# CPU_USB2_USB3_PHY.net
KiCad netlist of a schematic drawn in Altium Designer
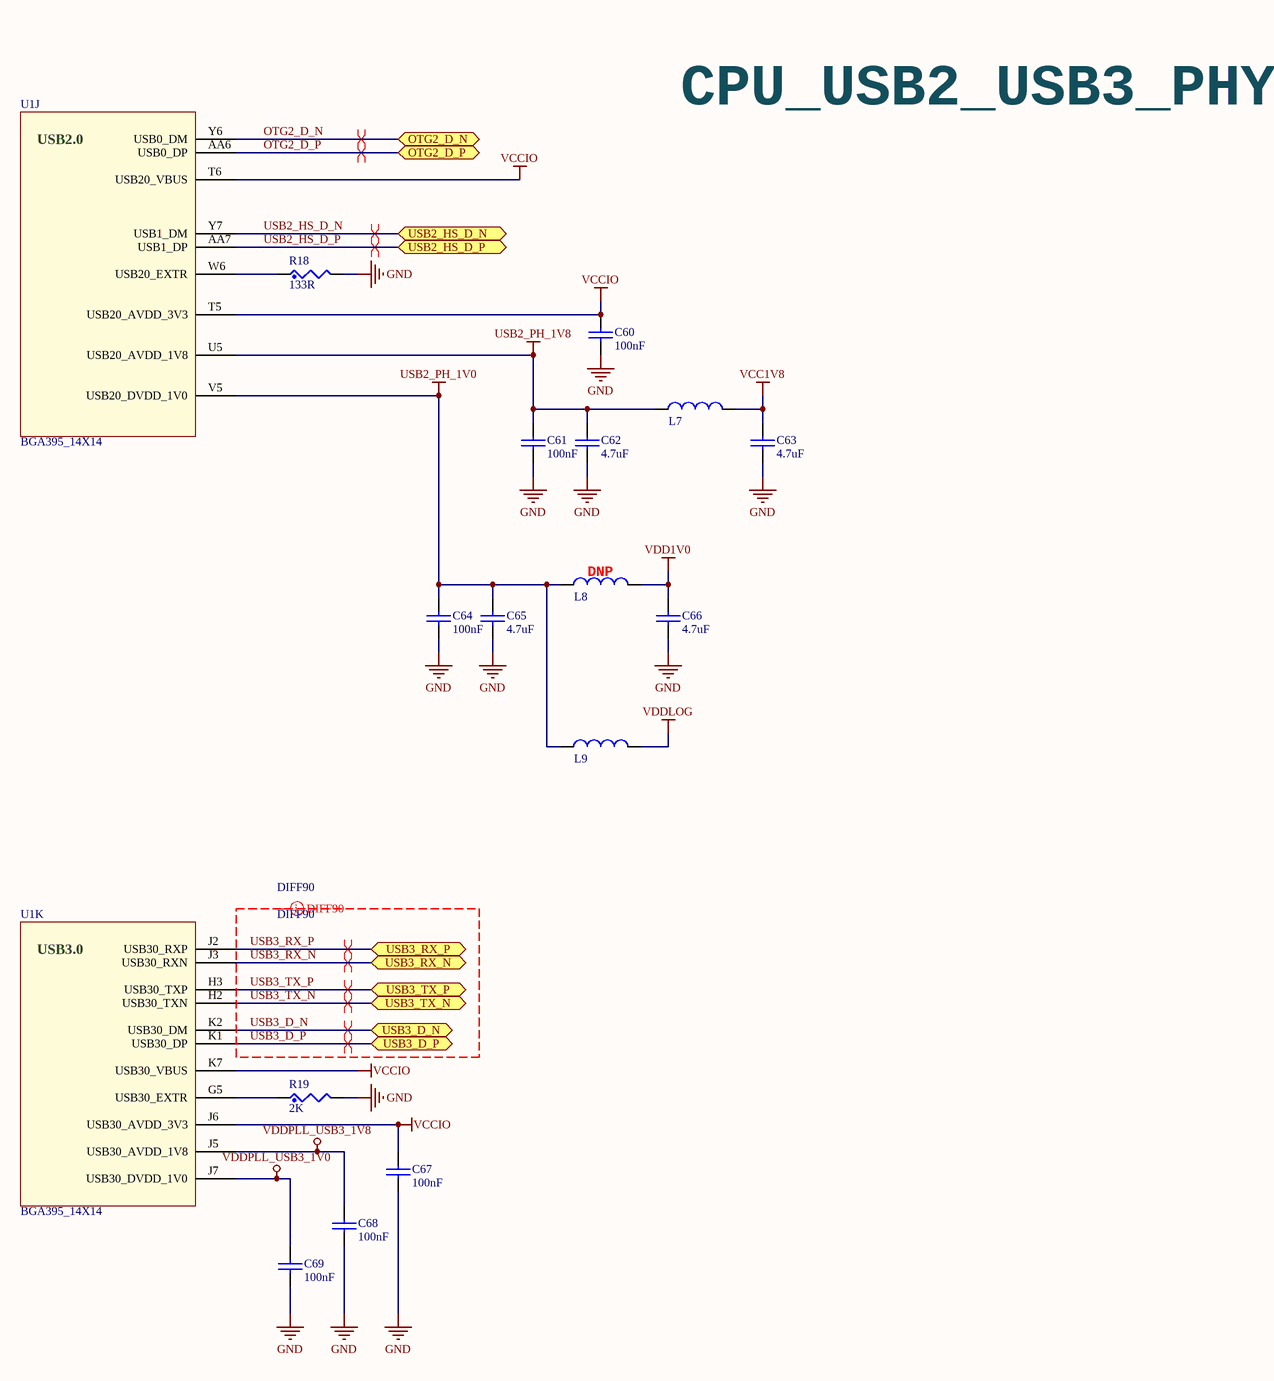
[diagram p0: CPU_USB2_USB3_PHY.SchDoc]

(export (version "E")
  (design (tool "Eeschema 10.0.6"))
  (components
    (comp (ref "C60")
      (value "100nF")
      (footprint "0402_CC - C")
      (libsource (lib "AAR_RockChip_RK3328") (part "CAP_NP"))
    )
    (comp (ref "C61")
      (value "100nF")
      (footprint "0402_CC - C")
      (libsource (lib "AAR_RockChip_RK3328") (part "CAP_NP"))
    )
    (comp (ref "C62")
      (value "4.7uF")
      (footprint "0402_CC - C")
      (libsource (lib "AAR_RockChip_RK3328") (part "CAP_NP"))
    )
    (comp (ref "C63")
      (value "4.7uF")
      (footprint "0402_CC - C")
      (libsource (lib "AAR_RockChip_RK3328") (part "CAP_NP"))
    )
    (comp (ref "C64")
      (value "100nF")
      (footprint "0402_CC - C")
      (libsource (lib "AAR_RockChip_RK3328") (part "CAP_NP"))
    )
    (comp (ref "C65")
      (value "4.7uF")
      (footprint "0402_CC - C")
      (libsource (lib "AAR_RockChip_RK3328") (part "CAP_NP"))
    )
    (comp (ref "C66")
      (value "4.7uF")
      (footprint "0402_CC - C")
      (libsource (lib "AAR_RockChip_RK3328") (part "CAP_NP"))
    )
    (comp (ref "C67")
      (value "100nF")
      (footprint "0402_CC - C")
      (libsource (lib "AAR_RockChip_RK3328") (part "CAP_NP"))
    )
    (comp (ref "C68")
      (value "100nF")
      (footprint "0402_CC - C")
      (libsource (lib "AAR_RockChip_RK3328") (part "CAP_NP"))
    )
    (comp (ref "C69")
      (value "100nF")
      (footprint "0402_CC - C")
      (libsource (lib "AAR_RockChip_RK3328") (part "CAP_NP"))
    )
    (comp (ref "L7")
      (value "INDCHIP")
      (footprint "0603_C_Inductor")
      (description "Fixed Inductors  TDK, By AAR")
      (libsource (lib "AAR_RockChip_RK3328") (part "INDCHIP"))
    )
    (comp (ref "L8")
      (value "INDCHIP")
      (footprint "0603_C_Inductor")
      (description "Fixed Inductors  TDK, By AAR")
      (libsource (lib "AAR_RockChip_RK3328") (part "INDCHIP"))
    )
    (comp (ref "L9")
      (value "INDCHIP")
      (footprint "0603_C_Inductor")
      (description "Fixed Inductors  TDK, By AAR")
      (libsource (lib "AAR_RockChip_RK3328") (part "INDCHIP"))
    )
    (comp (ref "R18")
      (value "133R")
      (footprint "0402_CR")
      (libsource (lib "AAR_RockChip_RK3328") (part "RES"))
    )
    (comp (ref "R19") (value "2K") (footprint "0402_CR") (libsource (lib "AAR_RockChip_RK3328") (part "RES")))
    (comp (ref "U1")
      (value "BGA395_14X14")
      (footprint "BGA395C65P21X21_1750X1750X117")
      (description "By AAR")
      (libsource (lib "AAR_RockChip_RK3328") (part "RK3328"))
    )
  )
  (nets
    (net (code "1") (name "/OTG2_D_N") (class "Default")
      (node (ref "U1") (pin "Y6") (pinfunction "USB0_DM_Y6") (pintype "passive"))
    )
    (net (code "2") (name "/OTG2_D_P") (class "Default")
      (node (ref "U1") (pin "AA6") (pinfunction "USB0_DP_AA6") (pintype "passive"))
    )
    (net (code "3") (name "/USB2_HS_D_N") (class "Default")
      (node (ref "U1") (pin "Y7") (pinfunction "USB1_DM_Y7") (pintype "passive"))
    )
    (net (code "4") (name "/USB2_HS_D_P") (class "Default")
      (node (ref "U1") (pin "AA7") (pinfunction "USB1_DP_AA7") (pintype "passive"))
    )
    (net (code "5") (name "/USB3_D_N") (class "Default")
      (node (ref "U1") (pin "K2") (pinfunction "USB30_DM_K2") (pintype "passive"))
    )
    (net (code "6") (name "/USB3_D_P") (class "Default")
      (node (ref "U1") (pin "K1") (pinfunction "USB30_DP_K1") (pintype "passive"))
    )
    (net (code "7") (name "/USB3_RX_N") (class "Default")
      (node (ref "U1") (pin "J3") (pinfunction "USB30_RXN_J3") (pintype "passive"))
    )
    (net (code "8") (name "/USB3_RX_P") (class "Default")
      (node (ref "U1") (pin "J2") (pinfunction "USB30_RXP_J2") (pintype "passive"))
    )
    (net (code "9") (name "/USB3_TX_N") (class "Default")
      (node (ref "U1") (pin "H2") (pinfunction "USB30_TXN_H2") (pintype "passive"))
    )
    (net (code "10") (name "/USB3_TX_P") (class "Default")
      (node (ref "U1") (pin "H3") (pinfunction "USB30_TXP_H3") (pintype "passive"))
    )
    (net (code "11") (name "GND") (class "Default")
      (node (ref "C60") (pin "2") (pinfunction "2_2") (pintype "passive"))
      (node (ref "C61") (pin "2") (pinfunction "2_2") (pintype "passive"))
      (node (ref "C62") (pin "2") (pinfunction "2_2") (pintype "passive"))
      (node (ref "C63") (pin "2") (pinfunction "2_2") (pintype "passive"))
      (node (ref "C64") (pin "2") (pinfunction "2_2") (pintype "passive"))
      (node (ref "C65") (pin "2") (pinfunction "2_2") (pintype "passive"))
      (node (ref "C66") (pin "2") (pinfunction "2_2") (pintype "passive"))
      (node (ref "C67") (pin "2") (pinfunction "2_2") (pintype "passive"))
      (node (ref "C68") (pin "2") (pinfunction "2_2") (pintype "passive"))
      (node (ref "C69") (pin "2") (pinfunction "2_2") (pintype "passive"))
      (node (ref "R18") (pin "2") (pinfunction "2_2") (pintype "passive"))
      (node (ref "R19") (pin "2") (pinfunction "2_2") (pintype "passive"))
    )
    (net (code "12") (name "Net-(U1J-USB20_EXTR)") (class "Default")
      (node (ref "R18") (pin "1") (pinfunction "1_1") (pintype "passive"))
      (node (ref "U1") (pin "W6") (pinfunction "USB20_EXTR_W6") (pintype "passive"))
    )
    (net (code "13") (name "Net-(U1K-USB30_EXTR)") (class "Default")
      (node (ref "R19") (pin "1") (pinfunction "1_1") (pintype "passive"))
      (node (ref "U1") (pin "G5") (pinfunction "USB30_EXTR_G5") (pintype "passive"))
    )
    (net (code "14") (name "USB2_PH_1V0") (class "Default")
      (node (ref "C64") (pin "1") (pinfunction "1_1") (pintype "passive"))
      (node (ref "C65") (pin "1") (pinfunction "1_1") (pintype "passive"))
      (node (ref "L8") (pin "1") (pinfunction "1_1") (pintype "passive"))
      (node (ref "L9") (pin "1") (pinfunction "1_1") (pintype "passive"))
      (node (ref "U1") (pin "V5") (pinfunction "USB20_DVDD_1V0_V5") (pintype "passive"))
    )
    (net (code "15") (name "USB2_PH_1V8") (class "Default")
      (node (ref "C61") (pin "1") (pinfunction "1_1") (pintype "passive"))
      (node (ref "C62") (pin "1") (pinfunction "1_1") (pintype "passive"))
      (node (ref "L7") (pin "1") (pinfunction "1_1") (pintype "passive"))
      (node (ref "U1") (pin "U5") (pinfunction "USB20_AVDD_1V8_U5") (pintype "passive"))
    )
    (net (code "16") (name "VCC1V8") (class "Default")
      (node (ref "C63") (pin "1") (pinfunction "1_1") (pintype "passive"))
      (node (ref "L7") (pin "2") (pinfunction "2_2") (pintype "passive"))
    )
    (net (code "17") (name "VCCIO") (class "Default")
      (node (ref "C60") (pin "1") (pinfunction "1_1") (pintype "passive"))
      (node (ref "C67") (pin "1") (pinfunction "1_1") (pintype "passive"))
      (node (ref "U1") (pin "J6") (pinfunction "USB30_AVDD_3V3_J6") (pintype "passive"))
      (node (ref "U1") (pin "K7") (pinfunction "USB30_VBUS_K7") (pintype "passive"))
      (node (ref "U1") (pin "T5") (pinfunction "USB20_AVDD_3V3_T5") (pintype "passive"))
      (node (ref "U1") (pin "T6") (pinfunction "USB20_VBUS_T6") (pintype "passive"))
    )
    (net (code "18") (name "VDD1V0") (class "Default")
      (node (ref "C66") (pin "1") (pinfunction "1_1") (pintype "passive"))
      (node (ref "L8") (pin "2") (pinfunction "2_2") (pintype "passive"))
    )
    (net (code "19") (name "VDDLOG") (class "Default")
      (node (ref "L9") (pin "2") (pinfunction "2_2") (pintype "passive"))
    )
    (net (code "20") (name "VDDPLL_USB3_1V0") (class "Default")
      (node (ref "C69") (pin "1") (pinfunction "1_1") (pintype "passive"))
      (node (ref "U1") (pin "J7") (pinfunction "USB30_DVDD_1V0_J7") (pintype "passive"))
    )
    (net (code "21") (name "VDDPLL_USB3_1V8") (class "Default")
      (node (ref "C68") (pin "1") (pinfunction "1_1") (pintype "passive"))
      (node (ref "U1") (pin "J5") (pinfunction "USB30_AVDD_1V8_J5") (pintype "passive"))
    )
  )
)
